# SchemaPanier.net
KiCad netlist of a schematic drawn in Altium Designer
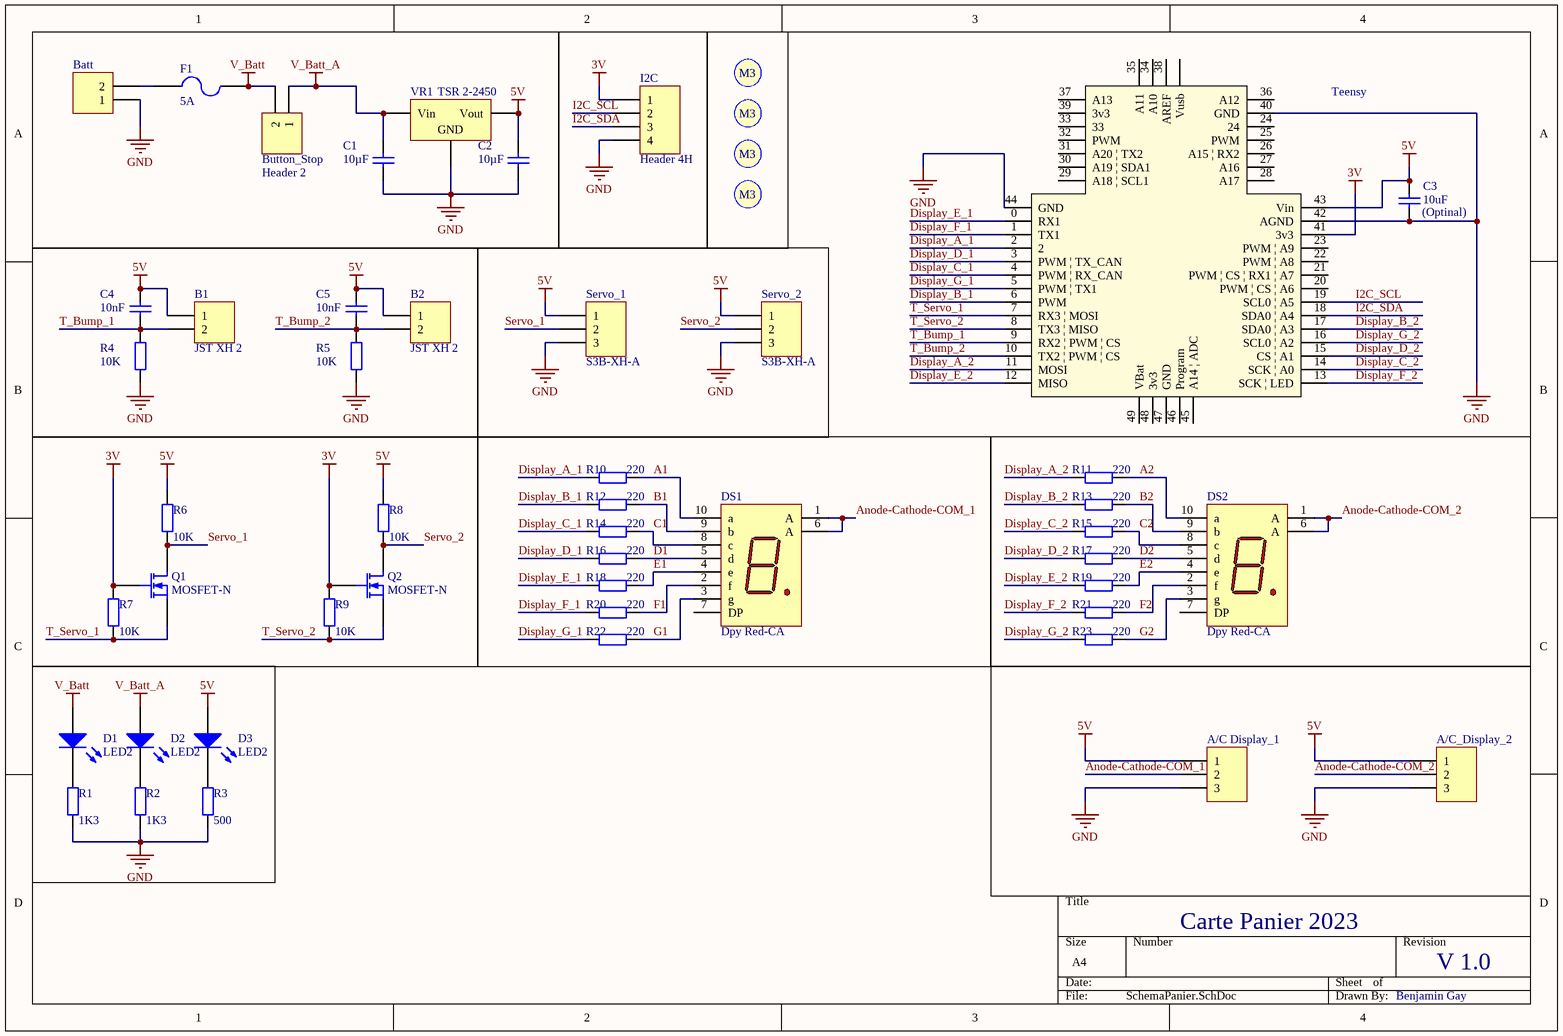
[diagram p0: SchemaPanier.SchDoc]

(export (version "E")
  (design (tool "Eeschema 10.0.6"))
  (components
    (comp (ref "A/C Display_1")
      (value "Common_7-segments")
      (footprint "HDR1X3")
      (description "Header, 3-Pin")
      (fields (field (name "PUBLISHER") "Altium Limited"))
      (libsource (lib "Miscellaneous Connectors") (part "Header 3"))
    )
    (comp (ref "A/C_Display_2")
      (value "Common_7-segments")
      (footprint "HDR1X3")
      (description "Header, 3-Pin")
      (fields (field (name "PUBLISHER") "Altium Limited"))
      (libsource (lib "Miscellaneous Connectors") (part "Header 3"))
    )
    (comp (ref "B1")
      (value "JST XH 2")
      (footprint "S2B-XH-A")
      (description "Header, 2-Pin")
      (fields (field (name "PUBLISHER") "Altium Limited"))
      (libsource (lib "Miscellaneous Connectors") (part "Header 2"))
    )
    (comp (ref "B2")
      (value "JST XH 2")
      (footprint "S2B-XH-A")
      (description "Header, 2-Pin")
      (fields (field (name "PUBLISHER") "Altium Limited"))
      (libsource (lib "Miscellaneous Connectors") (part "Header 2"))
    )
    (comp (ref "Batt")
      (value "~")
      (footprint "Battery SALE")
      (description "Header, 2-Pin")
      (fields (field (name "PUBLISHER") "Altium Limited"))
      (libsource (lib "") (part "Header 2_1"))
    )
    (comp (ref "Button_Stop")
      (value "Header 2")
      (footprint "Molex_MiniFitJr_2x1H")
      (description "Header, 2-Pin")
      (fields (field (name "PUBLISHER") "Altium Limited"))
      (libsource (lib "") (part "Header 2_2"))
    )
    (comp (ref "C1")
      (value "10µF")
      (footprint "Capacitor 1206")
      (description "Capacitor")
      (fields (field (name "Comment") "Cap") (field (name "PUBLISHER") "Altium Limited"))
      (libsource (lib "Miscellaneous Devices") (part "Cap"))
    )
    (comp (ref "C2")
      (value "10µF")
      (footprint "Capacitor 1206")
      (description "Capacitor")
      (fields (field (name "Comment") "Cap") (field (name "PUBLISHER") "Altium Limited"))
      (libsource (lib "Miscellaneous Devices") (part "Cap"))
    )
    (comp (ref "C3")
      (value "(Optinal)")
      (footprint "Capacitor 1206")
      (description "Capacitor")
      (fields (field (name "ALTIUM_VALUE") "10uF") (field (name "PUBLISHER") "Altium Limited"))
      (libsource (lib "Miscellaneous Devices") (part "Cap"))
    )
    (comp (ref "C4")
      (value "10nF")
      (footprint "Capacitor 1206")
      (description "Capacitor")
      (fields (field (name "Comment") "Cap") (field (name "PUBLISHER") "Altium Limited"))
      (libsource (lib "Miscellaneous Devices") (part "Cap"))
    )
    (comp (ref "C5")
      (value "10nF")
      (footprint "Capacitor 1206")
      (description "Capacitor")
      (fields (field (name "Comment") "Cap") (field (name "PUBLISHER") "Altium Limited"))
      (libsource (lib "Miscellaneous Devices") (part "Cap"))
    )
    (comp (ref "D1")
      (value "LED2")
      (footprint "KP-3216SEC")
      (description "Typical RED, GREEN, YELLOW, AMBER GaAs LED")
      (fields (field (name "PUBLISHER") "Altium Limited"))
      (libsource (lib "Miscellaneous Devices") (part "LED2"))
    )
    (comp (ref "D2")
      (value "LED2")
      (footprint "KP-3216SEC")
      (description "Typical RED, GREEN, YELLOW, AMBER GaAs LED")
      (fields (field (name "PUBLISHER") "Altium Limited"))
      (libsource (lib "Miscellaneous Devices") (part "LED2"))
    )
    (comp (ref "D3")
      (value "LED2")
      (footprint "KP-3216SEC")
      (description "Typical RED, GREEN, YELLOW, AMBER GaAs LED")
      (fields (field (name "PUBLISHER") "Altium Limited"))
      (libsource (lib "Miscellaneous Devices") (part "LED2"))
    )
    (comp (ref "DS1")
      (value "Dpy Red-CA")
      (footprint "7 segments 5082-7731")
      (description "7.62 mm Black Surface HER 7-Segment Display: CA, RH DP")
      (fields (field (name "PUBLISHER") "Altium Limited"))
      (libsource (lib "Miscellaneous Devices") (part "Dpy Red-CA"))
    )
    (comp (ref "DS2")
      (value "Dpy Red-CA")
      (footprint "7 segments 5082-7731")
      (description "7.62 mm Black Surface HER 7-Segment Display: CA, RH DP")
      (fields (field (name "PUBLISHER") "Altium Limited"))
      (libsource (lib "Miscellaneous Devices") (part "Dpy Red-CA"))
    )
    (comp (ref "F1")
      (value "5A")
      (footprint "Fuse")
      (description "Fuse")
      (fields (field (name "PUBLISHER") "Altium Limited"))
      (libsource (lib "Miscellaneous Devices") (part "Fuse 2"))
    )
    (comp (ref "I2C")
      (value "Header 4H")
      (footprint "S4B-XH-A")
      (description "Header, 4-Pin, Right Angle")
      (fields (field (name "PUBLISHER") "Altium Limited"))
      (libsource (lib "Miscellaneous Connectors") (part "Header 4H"))
    )
    (comp (ref "Q1")
      (value "MOSFET-N")
      (footprint "SOT23_M")
      (description "N-Channel MOSFET")
      (fields (field (name "PUBLISHER") "Altium Limited"))
      (libsource (lib "Miscellaneous Devices") (part "MOSFET-N"))
    )
    (comp (ref "Q2")
      (value "MOSFET-N")
      (footprint "SOT23_M")
      (description "N-Channel MOSFET")
      (fields (field (name "PUBLISHER") "Altium Limited"))
      (libsource (lib "Miscellaneous Devices") (part "MOSFET-N"))
    )
    (comp (ref "R1")
      (value "1K3")
      (footprint "Resistor 1206")
      (description "Resistor")
      (fields (field (name "PUBLISHER") "Altium Limited"))
      (libsource (lib "Miscellaneous Devices") (part "Res2"))
    )
    (comp (ref "R2")
      (value "1K3")
      (footprint "Resistor 1206")
      (description "Resistor")
      (fields (field (name "PUBLISHER") "Altium Limited"))
      (libsource (lib "Miscellaneous Devices") (part "Res2"))
    )
    (comp (ref "R3")
      (value "500")
      (footprint "Resistor 1206")
      (description "Resistor")
      (fields (field (name "PUBLISHER") "Altium Limited"))
      (libsource (lib "Miscellaneous Devices") (part "Res2"))
    )
    (comp (ref "R4")
      (value "10K")
      (footprint "Resistor 1206")
      (description "Resistor")
      (fields (field (name "Comment") "Res2") (field (name "PUBLISHER") "Altium Limited"))
      (libsource (lib "") (part "Res2_2"))
    )
    (comp (ref "R5")
      (value "10K")
      (footprint "Resistor 1206")
      (description "Resistor")
      (fields (field (name "Comment") "Res2") (field (name "PUBLISHER") "Altium Limited"))
      (libsource (lib "") (part "Res2_2"))
    )
    (comp (ref "R6")
      (value "10K")
      (footprint "Resistor 1206")
      (description "Resistor")
      (fields (field (name "PUBLISHER") "Altium Limited"))
      (libsource (lib "Miscellaneous Devices") (part "Res2"))
    )
    (comp (ref "R7")
      (value "10K")
      (footprint "Resistor 1206")
      (description "Resistor")
      (fields (field (name "PUBLISHER") "Altium Limited"))
      (libsource (lib "Miscellaneous Devices") (part "Res2"))
    )
    (comp (ref "R8")
      (value "10K")
      (footprint "Resistor 1206")
      (description "Resistor")
      (fields (field (name "PUBLISHER") "Altium Limited"))
      (libsource (lib "Miscellaneous Devices") (part "Res2"))
    )
    (comp (ref "R9")
      (value "10K")
      (footprint "Resistor 1206")
      (description "Resistor")
      (fields (field (name "PUBLISHER") "Altium Limited"))
      (libsource (lib "Miscellaneous Devices") (part "Res2"))
    )
    (comp (ref "R10")
      (value "220")
      (footprint "Resistor 1206")
      (description "Resistor")
      (fields (field (name "Comment") "Res2") (field (name "PUBLISHER") "Altium Limited"))
      (libsource (lib "") (part "Res2_1"))
    )
    (comp (ref "R11")
      (value "220")
      (footprint "Resistor 1206")
      (description "Resistor")
      (fields (field (name "Comment") "Res2") (field (name "PUBLISHER") "Altium Limited"))
      (libsource (lib "") (part "Res2_1"))
    )
    (comp (ref "R12")
      (value "220")
      (footprint "Resistor 1206")
      (description "Resistor")
      (fields (field (name "Comment") "Res2") (field (name "PUBLISHER") "Altium Limited"))
      (libsource (lib "") (part "Res2_1"))
    )
    (comp (ref "R13")
      (value "220")
      (footprint "Resistor 1206")
      (description "Resistor")
      (fields (field (name "Comment") "Res2") (field (name "PUBLISHER") "Altium Limited"))
      (libsource (lib "") (part "Res2_1"))
    )
    (comp (ref "R14")
      (value "220")
      (footprint "Resistor 1206")
      (description "Resistor")
      (fields (field (name "Comment") "Res2") (field (name "PUBLISHER") "Altium Limited"))
      (libsource (lib "") (part "Res2_1"))
    )
    (comp (ref "R15")
      (value "220")
      (footprint "Resistor 1206")
      (description "Resistor")
      (fields (field (name "Comment") "Res2") (field (name "PUBLISHER") "Altium Limited"))
      (libsource (lib "") (part "Res2_1"))
    )
    (comp (ref "R16")
      (value "220")
      (footprint "Resistor 1206")
      (description "Resistor")
      (fields (field (name "Comment") "Res2") (field (name "PUBLISHER") "Altium Limited"))
      (libsource (lib "") (part "Res2_1"))
    )
    (comp (ref "R17")
      (value "220")
      (footprint "Resistor 1206")
      (description "Resistor")
      (fields (field (name "Comment") "Res2") (field (name "PUBLISHER") "Altium Limited"))
      (libsource (lib "") (part "Res2_1"))
    )
    (comp (ref "R18")
      (value "220")
      (footprint "Resistor 1206")
      (description "Resistor")
      (fields (field (name "Comment") "Res2") (field (name "PUBLISHER") "Altium Limited"))
      (libsource (lib "") (part "Res2_1"))
    )
    (comp (ref "R19")
      (value "220")
      (footprint "Resistor 1206")
      (description "Resistor")
      (fields (field (name "Comment") "Res2") (field (name "PUBLISHER") "Altium Limited"))
      (libsource (lib "") (part "Res2_1"))
    )
    (comp (ref "R20")
      (value "220")
      (footprint "Resistor 1206")
      (description "Resistor")
      (fields (field (name "Comment") "Res2") (field (name "PUBLISHER") "Altium Limited"))
      (libsource (lib "") (part "Res2_1"))
    )
    (comp (ref "R21")
      (value "220")
      (footprint "Resistor 1206")
      (description "Resistor")
      (fields (field (name "Comment") "Res2") (field (name "PUBLISHER") "Altium Limited"))
      (libsource (lib "") (part "Res2_1"))
    )
    (comp (ref "R22")
      (value "220")
      (footprint "Resistor 1206")
      (description "Resistor")
      (fields (field (name "Comment") "Res2") (field (name "PUBLISHER") "Altium Limited"))
      (libsource (lib "") (part "Res2_1"))
    )
    (comp (ref "R23")
      (value "220")
      (footprint "Resistor 1206")
      (description "Resistor")
      (fields (field (name "Comment") "Res2") (field (name "PUBLISHER") "Altium Limited"))
      (libsource (lib "") (part "Res2_1"))
    )
    (comp (ref "S1")
      (value "Screw M3")
      (footprint "Screw M3")
      (libsource (lib "Robot_2019") (part "Screw M3"))
    )
    (comp (ref "S2")
      (value "Screw M3")
      (footprint "Screw M3")
      (libsource (lib "Robot_2019") (part "Screw M3"))
    )
    (comp (ref "S3")
      (value "Screw M3")
      (footprint "Screw M3")
      (libsource (lib "Robot_2019") (part "Screw M3"))
    )
    (comp (ref "S4")
      (value "Screw M3")
      (footprint "Screw M3")
      (libsource (lib "Robot_2019") (part "Screw M3"))
    )
    (comp (ref "Servo_1")
      (value "S3B-XH-A")
      (footprint "S3B-XH-A")
      (description "Header, 3-Pin, Right Angle")
      (fields (field (name "PUBLISHER") "Altium Limited"))
      (libsource (lib "Miscellaneous Connectors") (part "Header 3H"))
    )
    (comp (ref "Servo_2")
      (value "S3B-XH-A")
      (footprint "S3B-XH-A")
      (description "Header, 3-Pin, Right Angle")
      (fields (field (name "PUBLISHER") "Altium Limited"))
      (libsource (lib "Miscellaneous Connectors") (part "Header 3H"))
    )
    (comp (ref "Teensy")
      (value "Teensy 3.2")
      (footprint "teensy")
      (libsource (lib "Robot_2020") (part "teensy3.2"))
    )
    (comp (ref "VR1")
      (value "TSR 2-2450")
      (footprint "TRS")
      (description "Voltage Regulator")
      (fields (field (name "PUBLISHER") "Altium Limited"))
      (libsource (lib "Miscellaneous Devices") (part "Volt Reg"))
    )
  )
  (nets
    (net (code "1") (name "/A1") (class "Default")
      (node (ref "DS1") (pin "10") (pinfunction "a_10") (pintype "passive"))
      (node (ref "R10") (pin "2") (pinfunction "2_2") (pintype "passive"))
    )
    (net (code "2") (name "/A2") (class "Default")
      (node (ref "DS2") (pin "10") (pinfunction "a_10") (pintype "passive"))
      (node (ref "R11") (pin "2") (pinfunction "2_2") (pintype "passive"))
    )
    (net (code "3") (name "/Anode-Cathode-COM_1") (class "Default")
      (node (ref "A/C Display_1") (pin "2") (pinfunction "2_2") (pintype "passive"))
      (node (ref "DS1") (pin "1") (pinfunction "A_1") (pintype "passive"))
      (node (ref "DS1") (pin "6") (pinfunction "A_6") (pintype "passive"))
    )
    (net (code "4") (name "/Anode-Cathode-COM_2") (class "Default")
      (node (ref "A/C_Display_2") (pin "2") (pinfunction "2_2") (pintype "passive"))
      (node (ref "DS2") (pin "1") (pinfunction "A_1") (pintype "passive"))
      (node (ref "DS2") (pin "6") (pinfunction "A_6") (pintype "passive"))
    )
    (net (code "5") (name "/B1") (class "Default")
      (node (ref "DS1") (pin "9") (pinfunction "b_9") (pintype "passive"))
      (node (ref "R12") (pin "2") (pinfunction "2_2") (pintype "passive"))
    )
    (net (code "6") (name "/B2") (class "Default")
      (node (ref "DS2") (pin "9") (pinfunction "b_9") (pintype "passive"))
      (node (ref "R13") (pin "2") (pinfunction "2_2") (pintype "passive"))
    )
    (net (code "7") (name "/C1") (class "Default")
      (node (ref "DS1") (pin "8") (pinfunction "c_8") (pintype "passive"))
      (node (ref "R14") (pin "2") (pinfunction "2_2") (pintype "passive"))
    )
    (net (code "8") (name "/C2") (class "Default")
      (node (ref "DS2") (pin "8") (pinfunction "c_8") (pintype "passive"))
      (node (ref "R15") (pin "2") (pinfunction "2_2") (pintype "passive"))
    )
    (net (code "9") (name "/D1") (class "Default")
      (node (ref "DS1") (pin "5") (pinfunction "d_5") (pintype "passive"))
      (node (ref "R16") (pin "2") (pinfunction "2_2") (pintype "passive"))
    )
    (net (code "10") (name "/D2") (class "Default")
      (node (ref "DS2") (pin "5") (pinfunction "d_5") (pintype "passive"))
      (node (ref "R17") (pin "2") (pinfunction "2_2") (pintype "passive"))
    )
    (net (code "11") (name "/Display_A_1") (class "Default")
      (node (ref "R10") (pin "1") (pinfunction "1_1") (pintype "passive"))
      (node (ref "Teensy") (pin "2") (pinfunction "2_2") (pintype "passive"))
    )
    (net (code "12") (name "/Display_A_2") (class "Default")
      (node (ref "R11") (pin "1") (pinfunction "1_1") (pintype "passive"))
      (node (ref "Teensy") (pin "11") (pinfunction "MOSI_11") (pintype "passive"))
    )
    (net (code "13") (name "/Display_B_1") (class "Default")
      (node (ref "R12") (pin "1") (pinfunction "1_1") (pintype "passive"))
      (node (ref "Teensy") (pin "6") (pinfunction "PWM_6") (pintype "passive"))
    )
    (net (code "14") (name "/Display_B_2") (class "Default")
      (node (ref "R13") (pin "1") (pinfunction "1_1") (pintype "passive"))
      (node (ref "Teensy") (pin "17") (pinfunction "SDA0_¦_A3_17") (pintype "passive"))
    )
    (net (code "15") (name "/Display_C_1") (class "Default")
      (node (ref "R14") (pin "1") (pinfunction "1_1") (pintype "passive"))
      (node (ref "Teensy") (pin "4") (pinfunction "PWM_¦_RX_CAN_4") (pintype "passive"))
    )
    (net (code "16") (name "/Display_C_2") (class "Default")
      (node (ref "R15") (pin "1") (pinfunction "1_1") (pintype "passive"))
      (node (ref "Teensy") (pin "14") (pinfunction "SCK_¦_A0_14") (pintype "passive"))
    )
    (net (code "17") (name "/Display_D_1") (class "Default")
      (node (ref "R16") (pin "1") (pinfunction "1_1") (pintype "passive"))
      (node (ref "Teensy") (pin "3") (pinfunction "PWM_¦_TX_CAN_3") (pintype "passive"))
    )
    (net (code "18") (name "/Display_D_2") (class "Default")
      (node (ref "R17") (pin "1") (pinfunction "1_1") (pintype "passive"))
      (node (ref "Teensy") (pin "15") (pinfunction "CS_¦_A1_15") (pintype "passive"))
    )
    (net (code "19") (name "/Display_E_1") (class "Default")
      (node (ref "R18") (pin "1") (pinfunction "1_1") (pintype "passive"))
      (node (ref "Teensy") (pin "0") (pinfunction "RX1_0") (pintype "passive"))
    )
    (net (code "20") (name "/Display_E_2") (class "Default")
      (node (ref "R19") (pin "1") (pinfunction "1_1") (pintype "passive"))
      (node (ref "Teensy") (pin "12") (pinfunction "MISO_12") (pintype "passive"))
    )
    (net (code "21") (name "/Display_F_1") (class "Default")
      (node (ref "R20") (pin "1") (pinfunction "1_1") (pintype "passive"))
      (node (ref "Teensy") (pin "1") (pinfunction "TX1_1") (pintype "passive"))
    )
    (net (code "22") (name "/Display_F_2") (class "Default")
      (node (ref "R21") (pin "1") (pinfunction "1_1") (pintype "passive"))
      (node (ref "Teensy") (pin "13") (pinfunction "SCK_¦_LED_13") (pintype "passive"))
    )
    (net (code "23") (name "/Display_G_1") (class "Default")
      (node (ref "R22") (pin "1") (pinfunction "1_1") (pintype "passive"))
      (node (ref "Teensy") (pin "5") (pinfunction "PWM_¦_TX1_5") (pintype "passive"))
    )
    (net (code "24") (name "/Display_G_2") (class "Default")
      (node (ref "R23") (pin "1") (pinfunction "1_1") (pintype "passive"))
      (node (ref "Teensy") (pin "16") (pinfunction "SCL0_¦_A2_16") (pintype "passive"))
    )
    (net (code "25") (name "/E1") (class "Default")
      (node (ref "DS1") (pin "4") (pinfunction "e_4") (pintype "passive"))
      (node (ref "R18") (pin "2") (pinfunction "2_2") (pintype "passive"))
    )
    (net (code "26") (name "/E2") (class "Default")
      (node (ref "DS2") (pin "4") (pinfunction "e_4") (pintype "passive"))
      (node (ref "R19") (pin "2") (pinfunction "2_2") (pintype "passive"))
    )
    (net (code "27") (name "/F1") (class "Default")
      (node (ref "DS1") (pin "2") (pinfunction "f_2") (pintype "passive"))
      (node (ref "R20") (pin "2") (pinfunction "2_2") (pintype "passive"))
    )
    (net (code "28") (name "/F2") (class "Default")
      (node (ref "DS2") (pin "2") (pinfunction "f_2") (pintype "passive"))
      (node (ref "R21") (pin "2") (pinfunction "2_2") (pintype "passive"))
    )
    (net (code "29") (name "/G1") (class "Default")
      (node (ref "DS1") (pin "3") (pinfunction "g_3") (pintype "passive"))
      (node (ref "R22") (pin "2") (pinfunction "2_2") (pintype "passive"))
    )
    (net (code "30") (name "/G2") (class "Default")
      (node (ref "DS2") (pin "3") (pinfunction "g_3") (pintype "passive"))
      (node (ref "R23") (pin "2") (pinfunction "2_2") (pintype "passive"))
    )
    (net (code "31") (name "/I2C_SCL") (class "Default")
      (node (ref "I2C") (pin "2") (pinfunction "2_2") (pintype "passive"))
      (node (ref "Teensy") (pin "19") (pinfunction "SCL0_¦_A5_19") (pintype "passive"))
    )
    (net (code "32") (name "/I2C_SDA") (class "Default")
      (node (ref "I2C") (pin "3") (pinfunction "3_3") (pintype "passive"))
      (node (ref "Teensy") (pin "18") (pinfunction "SDA0_¦_A4_18") (pintype "passive"))
    )
    (net (code "33") (name "/Servo_1") (class "Default")
      (node (ref "Q1") (pin "1") (pinfunction "D_1") (pintype "passive"))
      (node (ref "R6") (pin "1") (pinfunction "1_1") (pintype "passive"))
      (node (ref "Servo_1") (pin "2") (pinfunction "2_2") (pintype "passive"))
    )
    (net (code "34") (name "/Servo_2") (class "Default")
      (node (ref "Q2") (pin "1") (pinfunction "D_1") (pintype "passive"))
      (node (ref "R8") (pin "1") (pinfunction "1_1") (pintype "passive"))
      (node (ref "Servo_2") (pin "2") (pinfunction "2_2") (pintype "passive"))
    )
    (net (code "35") (name "/T_Bump_1") (class "Default")
      (node (ref "B1") (pin "2") (pinfunction "2_2") (pintype "passive"))
      (node (ref "C4") (pin "1") (pinfunction "1_1") (pintype "passive"))
      (node (ref "R4") (pin "1") (pinfunction "1_1") (pintype "passive"))
      (node (ref "Teensy") (pin "9") (pinfunction "RX2_¦_PWM_¦_CS_9") (pintype "passive"))
    )
    (net (code "36") (name "/T_Bump_2") (class "Default")
      (node (ref "B2") (pin "2") (pinfunction "2_2") (pintype "passive"))
      (node (ref "C5") (pin "1") (pinfunction "1_1") (pintype "passive"))
      (node (ref "R5") (pin "1") (pinfunction "1_1") (pintype "passive"))
      (node (ref "Teensy") (pin "10") (pinfunction "TX2_¦_PWM_¦_CS_10") (pintype "passive"))
    )
    (net (code "37") (name "/T_Servo_1") (class "Default")
      (node (ref "Q1") (pin "3") (pinfunction "S_3") (pintype "passive"))
      (node (ref "R7") (pin "1") (pinfunction "1_1") (pintype "passive"))
      (node (ref "Teensy") (pin "7") (pinfunction "RX3_¦_MOSI_7") (pintype "passive"))
    )
    (net (code "38") (name "/T_Servo_2") (class "Default")
      (node (ref "Q2") (pin "3") (pinfunction "S_3") (pintype "passive"))
      (node (ref "R9") (pin "1") (pinfunction "1_1") (pintype "passive"))
      (node (ref "Teensy") (pin "8") (pinfunction "TX3_¦_MISO_8") (pintype "passive"))
    )
    (net (code "39") (name "3V") (class "Default")
      (node (ref "I2C") (pin "1") (pinfunction "1_1") (pintype "passive"))
      (node (ref "Q1") (pin "2") (pinfunction "G_2") (pintype "passive"))
      (node (ref "Q2") (pin "2") (pinfunction "G_2") (pintype "passive"))
      (node (ref "R7") (pin "2") (pinfunction "2_2") (pintype "passive"))
      (node (ref "R9") (pin "2") (pinfunction "2_2") (pintype "passive"))
      (node (ref "Teensy") (pin "41") (pinfunction "3v3_41") (pintype "passive"))
    )
    (net (code "40") (name "5V") (class "Default")
      (node (ref "A/C Display_1") (pin "1") (pinfunction "1_1") (pintype "passive"))
      (node (ref "A/C_Display_2") (pin "1") (pinfunction "1_1") (pintype "passive"))
      (node (ref "B1") (pin "1") (pinfunction "1_1") (pintype "passive"))
      (node (ref "B2") (pin "1") (pinfunction "1_1") (pintype "passive"))
      (node (ref "C2") (pin "2") (pinfunction "2_2") (pintype "passive"))
      (node (ref "C3") (pin "2") (pinfunction "2_2") (pintype "passive"))
      (node (ref "C4") (pin "2") (pinfunction "2_2") (pintype "passive"))
      (node (ref "C5") (pin "2") (pinfunction "2_2") (pintype "passive"))
      (node (ref "D3") (pin "1") (pinfunction "A_1") (pintype "passive"))
      (node (ref "R6") (pin "2") (pinfunction "2_2") (pintype "passive"))
      (node (ref "R8") (pin "2") (pinfunction "2_2") (pintype "passive"))
      (node (ref "Servo_1") (pin "1") (pinfunction "1_1") (pintype "passive"))
      (node (ref "Servo_2") (pin "1") (pinfunction "1_1") (pintype "passive"))
      (node (ref "Teensy") (pin "43") (pinfunction "Vin_43") (pintype "passive"))
      (node (ref "VR1") (pin "3") (pinfunction "Vout_3") (pintype "passive"))
    )
    (net (code "41") (name "GND") (class "Default")
      (node (ref "A/C Display_1") (pin "3") (pinfunction "3_3") (pintype "passive"))
      (node (ref "A/C_Display_2") (pin "3") (pinfunction "3_3") (pintype "passive"))
      (node (ref "Batt") (pin "1") (pinfunction "1_1") (pintype "passive"))
      (node (ref "C1") (pin "1") (pinfunction "1_1") (pintype "passive"))
      (node (ref "C2") (pin "1") (pinfunction "1_1") (pintype "passive"))
      (node (ref "C3") (pin "1") (pinfunction "1_1") (pintype "passive"))
      (node (ref "I2C") (pin "4") (pinfunction "4_4") (pintype "passive"))
      (node (ref "R1") (pin "1") (pinfunction "1_1") (pintype "passive"))
      (node (ref "R2") (pin "1") (pinfunction "1_1") (pintype "passive"))
      (node (ref "R3") (pin "1") (pinfunction "1_1") (pintype "passive"))
      (node (ref "R4") (pin "2") (pinfunction "2_2") (pintype "passive"))
      (node (ref "R5") (pin "2") (pinfunction "2_2") (pintype "passive"))
      (node (ref "Servo_1") (pin "3") (pinfunction "3_3") (pintype "passive"))
      (node (ref "Servo_2") (pin "3") (pinfunction "3_3") (pintype "passive"))
      (node (ref "Teensy") (pin "40") (pinfunction "GND_40") (pintype "passive"))
      (node (ref "Teensy") (pin "42") (pinfunction "AGND_42") (pintype "passive"))
      (node (ref "Teensy") (pin "44") (pinfunction "GND_44") (pintype "passive"))
      (node (ref "VR1") (pin "2") (pinfunction "GND_2") (pintype "passive"))
    )
    (net (code "42") (name "Net-(Batt-Pad2)") (class "Default")
      (node (ref "Batt") (pin "2") (pinfunction "2_2") (pintype "passive"))
      (node (ref "F1") (pin "1") (pinfunction "1_1") (pintype "passive"))
    )
    (net (code "43") (name "Net-(D1-K)") (class "Default")
      (node (ref "D1") (pin "2") (pinfunction "K_2") (pintype "passive"))
      (node (ref "R1") (pin "2") (pinfunction "2_2") (pintype "passive"))
    )
    (net (code "44") (name "Net-(D2-K)") (class "Default")
      (node (ref "D2") (pin "2") (pinfunction "K_2") (pintype "passive"))
      (node (ref "R2") (pin "2") (pinfunction "2_2") (pintype "passive"))
    )
    (net (code "45") (name "Net-(D3-K)") (class "Default")
      (node (ref "D3") (pin "2") (pinfunction "K_2") (pintype "passive"))
      (node (ref "R3") (pin "2") (pinfunction "2_2") (pintype "passive"))
    )
    (net (code "46") (name "V_Batt") (class "Default")
      (node (ref "Button_Stop") (pin "2") (pinfunction "2_2") (pintype "passive"))
      (node (ref "D1") (pin "1") (pinfunction "A_1") (pintype "passive"))
      (node (ref "F1") (pin "2") (pinfunction "2_2") (pintype "passive"))
    )
    (net (code "47") (name "V_Batt_A") (class "Default")
      (node (ref "Button_Stop") (pin "1") (pinfunction "1_1") (pintype "passive"))
      (node (ref "C1") (pin "2") (pinfunction "2_2") (pintype "passive"))
      (node (ref "D2") (pin "1") (pinfunction "A_1") (pintype "passive"))
      (node (ref "VR1") (pin "1") (pinfunction "Vin_1") (pintype "passive"))
    )
    (net (code "48") (name "unconnected-(DS1-DP-Pad7)") (class "Default")
      (node (ref "DS1") (pin "7") (pinfunction "DP_7") (pintype "passive"))
    )
    (net (code "49") (name "unconnected-(DS2-DP-Pad7)") (class "Default")
      (node (ref "DS2") (pin "7") (pinfunction "DP_7") (pintype "passive"))
    )
    (net (code "50") (name "unconnected-(Teensy-3v3-Pad39)") (class "Default")
      (node (ref "Teensy") (pin "39") (pinfunction "3v3_39") (pintype "passive"))
    )
    (net (code "51") (name "unconnected-(Teensy-3v3-Pad48)") (class "Default")
      (node (ref "Teensy") (pin "48") (pinfunction "3v3_48") (pintype "passive"))
    )
    (net (code "52") (name "unconnected-(Teensy-A10-Pad34)") (class "Default")
      (node (ref "Teensy") (pin "34") (pinfunction "A10_34") (pintype "passive"))
    )
    (net (code "53") (name "unconnected-(Teensy-A11-Pad35)") (class "Default")
      (node (ref "Teensy") (pin "35") (pinfunction "A11_35") (pintype "passive"))
    )
    (net (code "54") (name "unconnected-(Teensy-A12-Pad36)") (class "Default")
      (node (ref "Teensy") (pin "36") (pinfunction "A12_36") (pintype "passive"))
    )
    (net (code "55") (name "unconnected-(Teensy-A13-Pad37)") (class "Default")
      (node (ref "Teensy") (pin "37") (pinfunction "A13_37") (pintype "passive"))
    )
    (net (code "56") (name "unconnected-(Teensy-A14_¦_ADC-Pad45)") (class "Default")
      (node (ref "Teensy") (pin "45") (pinfunction "A14_¦_ADC_45") (pintype "passive"))
    )
    (net (code "57") (name "unconnected-(Teensy-A15_¦_RX2-Pad26)") (class "Default")
      (node (ref "Teensy") (pin "26") (pinfunction "A15_¦_RX2_26") (pintype "passive"))
    )
    (net (code "58") (name "unconnected-(Teensy-A16-Pad27)") (class "Default")
      (node (ref "Teensy") (pin "27") (pinfunction "A16_27") (pintype "passive"))
    )
    (net (code "59") (name "unconnected-(Teensy-A17-Pad28)") (class "Default")
      (node (ref "Teensy") (pin "28") (pinfunction "A17_28") (pintype "passive"))
    )
    (net (code "60") (name "unconnected-(Teensy-A18_¦_SCL1-Pad29)") (class "Default")
      (node (ref "Teensy") (pin "29") (pinfunction "A18_¦_SCL1_29") (pintype "passive"))
    )
    (net (code "61") (name "unconnected-(Teensy-A19_¦_SDA1-Pad30)") (class "Default")
      (node (ref "Teensy") (pin "30") (pinfunction "A19_¦_SDA1_30") (pintype "passive"))
    )
    (net (code "62") (name "unconnected-(Teensy-A20_¦_TX2-Pad31)") (class "Default")
      (node (ref "Teensy") (pin "31") (pinfunction "A20_¦_TX2_31") (pintype "passive"))
    )
    (net (code "63") (name "unconnected-(Teensy-AREF-Pad38)") (class "Default")
      (node (ref "Teensy") (pin "38") (pinfunction "AREF_38") (pintype "passive"))
    )
    (net (code "64") (name "unconnected-(Teensy-GND-Pad47)") (class "Default")
      (node (ref "Teensy") (pin "47") (pinfunction "GND_47") (pintype "passive"))
    )
    (net (code "65") (name "unconnected-(Teensy-PWM-Pad25)") (class "Default")
      (node (ref "Teensy") (pin "25") (pinfunction "PWM_25") (pintype "passive"))
    )
    (net (code "66") (name "unconnected-(Teensy-PWM-Pad32)") (class "Default")
      (node (ref "Teensy") (pin "32") (pinfunction "PWM_32") (pintype "passive"))
    )
    (net (code "67") (name "unconnected-(Teensy-PWM_¦_A8-Pad22)") (class "Default")
      (node (ref "Teensy") (pin "22") (pinfunction "PWM_¦_A8_22") (pintype "passive"))
    )
    (net (code "68") (name "unconnected-(Teensy-PWM_¦_A9-Pad23)") (class "Default")
      (node (ref "Teensy") (pin "23") (pinfunction "PWM_¦_A9_23") (pintype "passive"))
    )
    (net (code "69") (name "unconnected-(Teensy-PWM_¦_CS_¦_A6-Pad20)") (class "Default")
      (node (ref "Teensy") (pin "20") (pinfunction "PWM_¦_CS_¦_A6_20") (pintype "passive"))
    )
    (net (code "70") (name "unconnected-(Teensy-PWM_¦_CS_¦_RX1_¦_A7-Pad21)") (class "Default")
      (node (ref "Teensy") (pin "21") (pinfunction "PWM_¦_CS_¦_RX1_¦_A7_21") (pintype "passive"))
    )
    (net (code "71") (name "unconnected-(Teensy-Pad24)") (class "Default")
      (node (ref "Teensy") (pin "24") (pinfunction "24_24") (pintype "passive"))
    )
    (net (code "72") (name "unconnected-(Teensy-Pad33)") (class "Default")
      (node (ref "Teensy") (pin "33") (pinfunction "33_33") (pintype "passive"))
    )
    (net (code "73") (name "unconnected-(Teensy-Program-Pad46)") (class "Default")
      (node (ref "Teensy") (pin "46") (pinfunction "Program_46") (pintype "passive"))
    )
    (net (code "74") (name "unconnected-(Teensy-VBat-Pad49)") (class "Default")
      (node (ref "Teensy") (pin "49") (pinfunction "VBat_49") (pintype "passive"))
    )
    (net (code "75") (name "unconnected-(Teensy-Vusb-Pad50)") (class "Default")
      (node (ref "Teensy") (pin "50") (pinfunction "Vusb_50") (pintype "passive"))
    )
  )
)
